# M304X.net
KiCad netlist of a schematic drawn in EAGLE
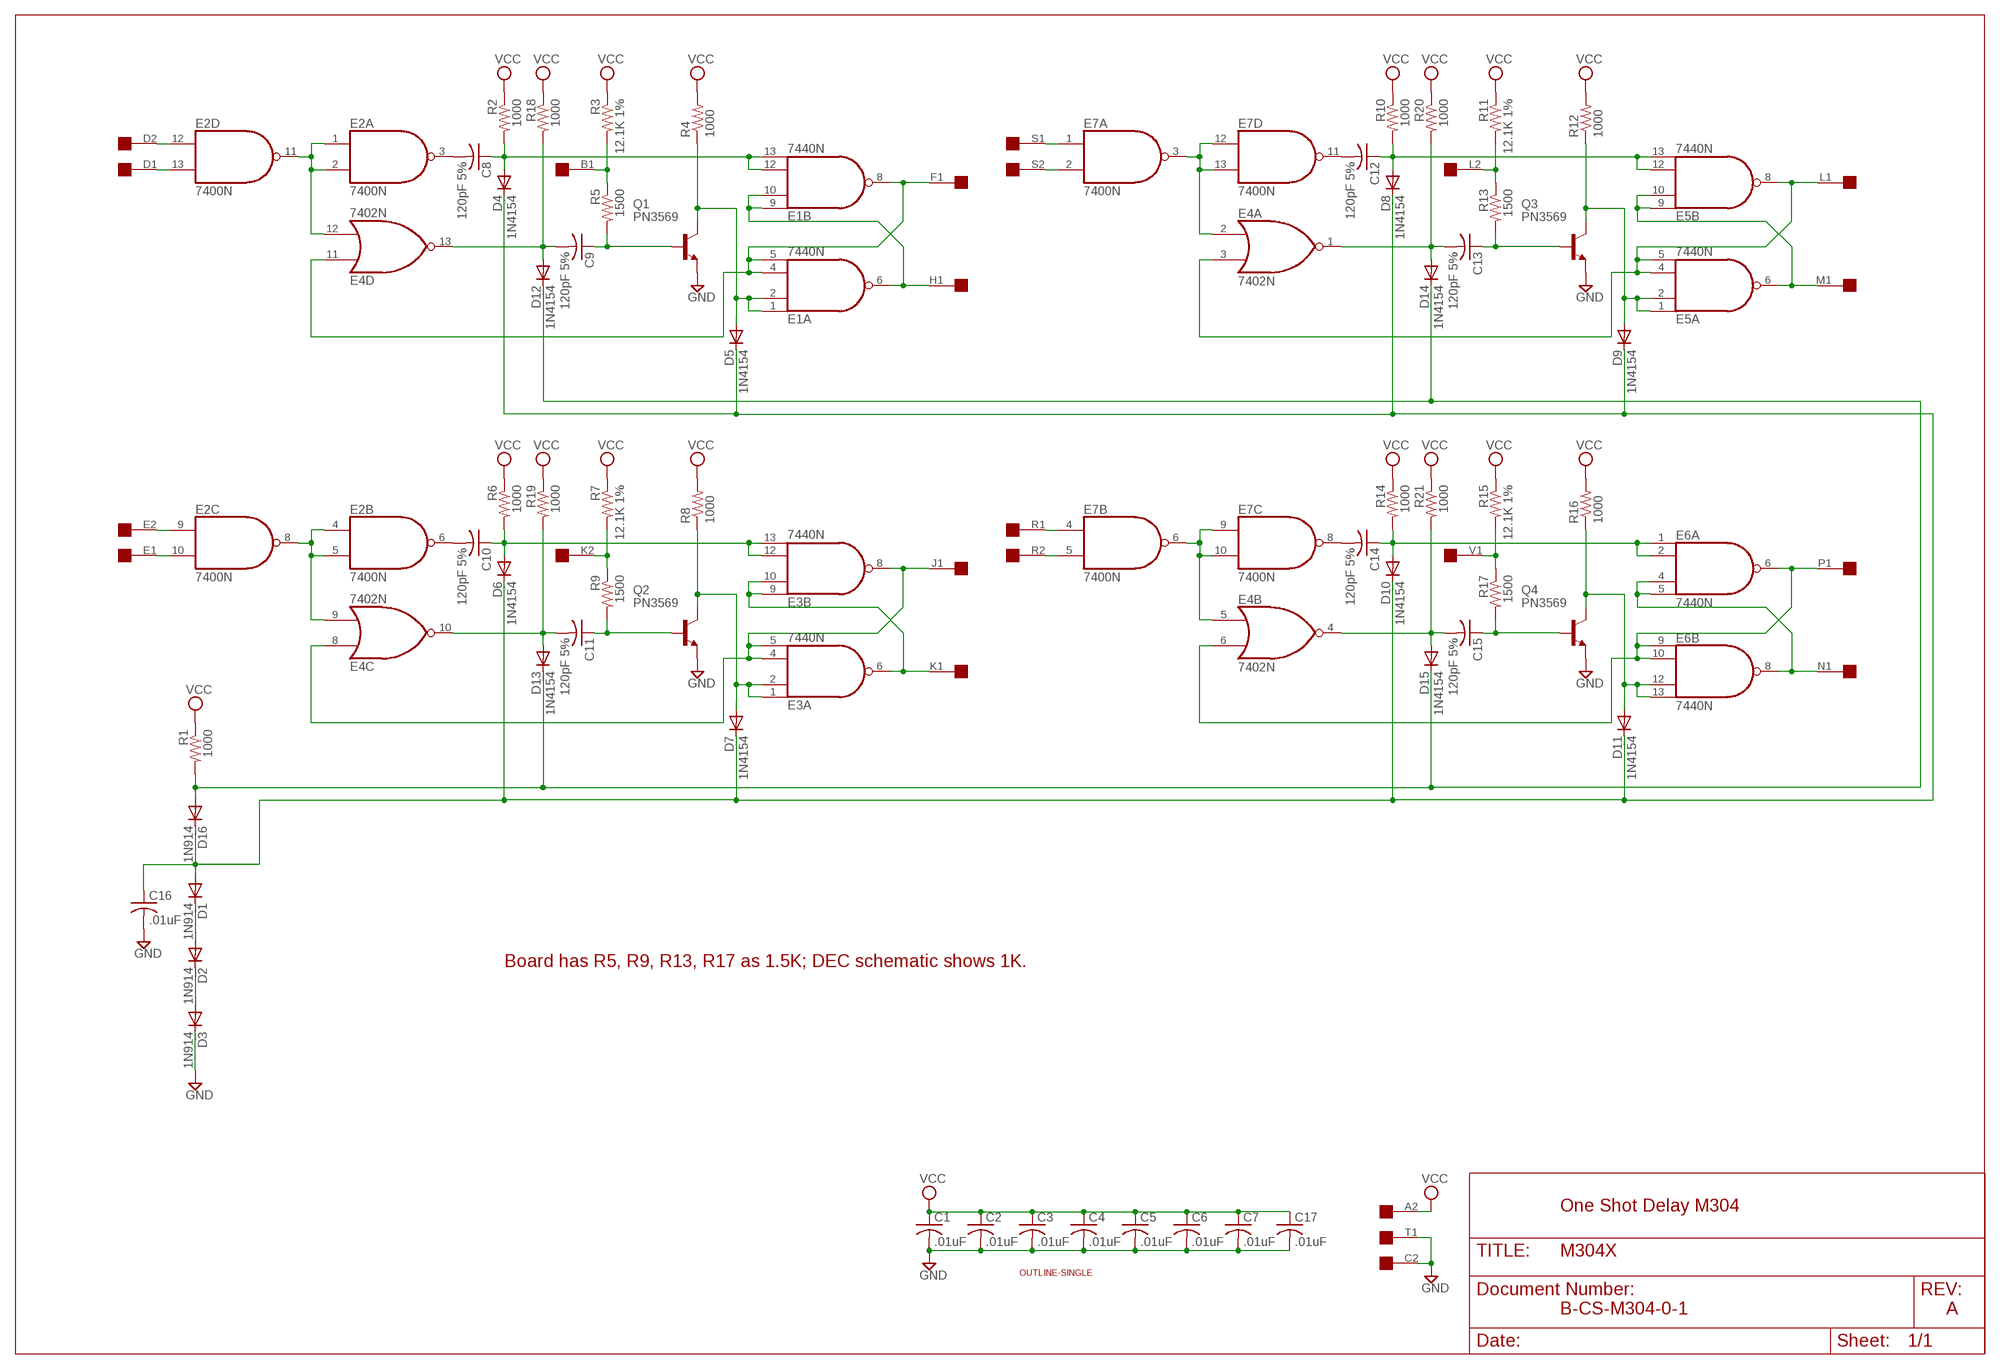
[diagram p0: schematic, sheet 1]

(export (version "E")
  (design (tool "Eeschema 10.0.6"))
  (components
    (comp (ref "C1")
      (value ".01uF")
      (footprint "eagle-import:C050-025X075")
      (libsource (lib "eagle-import") (part "C-US050-025X075"))
    )
    (comp (ref "C2")
      (value ".01uF")
      (footprint "eagle-import:C050-025X075")
      (libsource (lib "eagle-import") (part "C-US050-025X075"))
    )
    (comp (ref "C3")
      (value ".01uF")
      (footprint "eagle-import:C050-025X075")
      (libsource (lib "eagle-import") (part "C-US050-025X075"))
    )
    (comp (ref "C4")
      (value ".01uF")
      (footprint "eagle-import:C050-025X075")
      (libsource (lib "eagle-import") (part "C-US050-025X075"))
    )
    (comp (ref "C5")
      (value ".01uF")
      (footprint "eagle-import:C050-025X075")
      (libsource (lib "eagle-import") (part "C-US050-025X075"))
    )
    (comp (ref "C6")
      (value ".01uF")
      (footprint "eagle-import:C050-025X075")
      (libsource (lib "eagle-import") (part "C-US050-025X075"))
    )
    (comp (ref "C7")
      (value ".01uF")
      (footprint "eagle-import:C050-025X075")
      (libsource (lib "eagle-import") (part "C-US050-025X075"))
    )
    (comp (ref "C8")
      (value "120pF 5%")
      (footprint "eagle-import:C050-025X075")
      (libsource (lib "eagle-import") (part "C-US050-025X075"))
    )
    (comp (ref "C9")
      (value "120pF 5%")
      (footprint "eagle-import:C050-025X075")
      (libsource (lib "eagle-import") (part "C-US050-025X075"))
    )
    (comp (ref "C10")
      (value "120pF 5%")
      (footprint "eagle-import:C050-025X075")
      (libsource (lib "eagle-import") (part "C-US050-025X075"))
    )
    (comp (ref "C11")
      (value "120pF 5%")
      (footprint "eagle-import:C050-025X075")
      (libsource (lib "eagle-import") (part "C-US050-025X075"))
    )
    (comp (ref "C12")
      (value "120pF 5%")
      (footprint "eagle-import:C050-025X075")
      (libsource (lib "eagle-import") (part "C-US050-025X075"))
    )
    (comp (ref "C13")
      (value "120pF 5%")
      (footprint "eagle-import:C050-025X075")
      (libsource (lib "eagle-import") (part "C-US050-025X075"))
    )
    (comp (ref "C14")
      (value "120pF 5%")
      (footprint "eagle-import:C050-025X075")
      (libsource (lib "eagle-import") (part "C-US050-025X075"))
    )
    (comp (ref "C15")
      (value "120pF 5%")
      (footprint "eagle-import:C050-025X075")
      (libsource (lib "eagle-import") (part "C-US050-025X075"))
    )
    (comp (ref "C16")
      (value ".01uF")
      (footprint "eagle-import:C050-025X075")
      (libsource (lib "eagle-import") (part "C-US050-025X075"))
    )
    (comp (ref "C17")
      (value ".01uF")
      (footprint "eagle-import:C050-025X075")
      (libsource (lib "eagle-import") (part "C-US050-025X075"))
    )
    (comp (ref "D1")
      (value "1N914")
      (footprint "eagle-import:DO35-10")
      (libsource (lib "eagle-import") (part "1N4148DO35-10"))
    )
    (comp (ref "D2")
      (value "1N914")
      (footprint "eagle-import:DO35-10")
      (libsource (lib "eagle-import") (part "1N4148DO35-10"))
    )
    (comp (ref "D3")
      (value "1N914")
      (footprint "eagle-import:DO35-10")
      (libsource (lib "eagle-import") (part "1N4148DO35-10"))
    )
    (comp (ref "D4")
      (value "1N4154")
      (footprint "eagle-import:DO35-10")
      (libsource (lib "eagle-import") (part "1N4148DO35-10"))
    )
    (comp (ref "D5")
      (value "1N4154")
      (footprint "eagle-import:DO35-10")
      (libsource (lib "eagle-import") (part "1N4148DO35-10"))
    )
    (comp (ref "D6")
      (value "1N4154")
      (footprint "eagle-import:DO35-10")
      (libsource (lib "eagle-import") (part "1N4148DO35-10"))
    )
    (comp (ref "D7")
      (value "1N4154")
      (footprint "eagle-import:DO35-10")
      (libsource (lib "eagle-import") (part "1N4148DO35-10"))
    )
    (comp (ref "D8")
      (value "1N4154")
      (footprint "eagle-import:DO35-10")
      (libsource (lib "eagle-import") (part "1N4148DO35-10"))
    )
    (comp (ref "D9")
      (value "1N4154")
      (footprint "eagle-import:DO35-10")
      (libsource (lib "eagle-import") (part "1N4148DO35-10"))
    )
    (comp (ref "D10")
      (value "1N4154")
      (footprint "eagle-import:DO35-10")
      (libsource (lib "eagle-import") (part "1N4148DO35-10"))
    )
    (comp (ref "D11")
      (value "1N4154")
      (footprint "eagle-import:DO35-10")
      (libsource (lib "eagle-import") (part "1N4148DO35-10"))
    )
    (comp (ref "D12")
      (value "1N4154")
      (footprint "eagle-import:DO35-10")
      (libsource (lib "eagle-import") (part "1N4148DO35-10"))
    )
    (comp (ref "D13")
      (value "1N4154")
      (footprint "eagle-import:DO35-10")
      (libsource (lib "eagle-import") (part "1N4148DO35-10"))
    )
    (comp (ref "D14")
      (value "1N4154")
      (footprint "eagle-import:DO35-10")
      (libsource (lib "eagle-import") (part "1N4148DO35-10"))
    )
    (comp (ref "D15")
      (value "1N4154")
      (footprint "eagle-import:DO35-10")
      (libsource (lib "eagle-import") (part "1N4148DO35-10"))
    )
    (comp (ref "D16")
      (value "1N914")
      (footprint "eagle-import:DO35-10")
      (libsource (lib "eagle-import") (part "1N4148DO35-10"))
    )
    (comp (ref "E1")
      (value "7440N")
      (footprint "eagle-import:DIL14")
      (libsource (lib "eagle-import") (part "7420NS"))
    )
    (comp (ref "E2")
      (value "7400N")
      (footprint "eagle-import:DIL14")
      (libsource (lib "eagle-import") (part "7400N"))
    )
    (comp (ref "E3")
      (value "7440N")
      (footprint "eagle-import:DIL14")
      (libsource (lib "eagle-import") (part "7420NS"))
    )
    (comp (ref "E4")
      (value "7402N")
      (footprint "eagle-import:DIL14")
      (libsource (lib "eagle-import") (part "7402N"))
    )
    (comp (ref "E5")
      (value "7440N")
      (footprint "eagle-import:DIL14")
      (libsource (lib "eagle-import") (part "7420NS"))
    )
    (comp (ref "E6")
      (value "7440N")
      (footprint "eagle-import:DIL14")
      (libsource (lib "eagle-import") (part "7420NS"))
    )
    (comp (ref "E7")
      (value "7400N")
      (footprint "eagle-import:DIL14")
      (libsource (lib "eagle-import") (part "7400N"))
    )
    (comp (ref "Q1")
      (value "PN3569")
      (footprint "eagle-import:TO39")
      (libsource (lib "eagle-import") (part "-NPN-TO39-EBC2N3019"))
    )
    (comp (ref "Q2")
      (value "PN3569")
      (footprint "eagle-import:TO39")
      (libsource (lib "eagle-import") (part "-NPN-TO39-EBC2N3019"))
    )
    (comp (ref "Q3")
      (value "PN3569")
      (footprint "eagle-import:TO39")
      (libsource (lib "eagle-import") (part "-NPN-TO39-EBC2N3019"))
    )
    (comp (ref "Q4")
      (value "PN3569")
      (footprint "eagle-import:TO39")
      (libsource (lib "eagle-import") (part "-NPN-TO39-EBC2N3019"))
    )
    (comp (ref "R1")
      (value "1000")
      (footprint "eagle-import:0207_10")
      (libsource (lib "eagle-import") (part "R-US_0207/10"))
    )
    (comp (ref "R2")
      (value "1000")
      (footprint "eagle-import:0207_10")
      (libsource (lib "eagle-import") (part "R-US_0207/10"))
    )
    (comp (ref "R3")
      (value "12.1K 1%")
      (footprint "eagle-import:0207_15")
      (libsource (lib "eagle-import") (part "R-US_0207/15"))
    )
    (comp (ref "R4")
      (value "1000")
      (footprint "eagle-import:0207_10")
      (libsource (lib "eagle-import") (part "R-US_0207/10"))
    )
    (comp (ref "R5")
      (value "1500")
      (footprint "eagle-import:0207_10")
      (libsource (lib "eagle-import") (part "R-US_0207/10"))
    )
    (comp (ref "R6")
      (value "1000")
      (footprint "eagle-import:0207_10")
      (libsource (lib "eagle-import") (part "R-US_0207/10"))
    )
    (comp (ref "R7")
      (value "12.1K 1%")
      (footprint "eagle-import:0207_15")
      (libsource (lib "eagle-import") (part "R-US_0207/15"))
    )
    (comp (ref "R8")
      (value "1000")
      (footprint "eagle-import:0207_10")
      (libsource (lib "eagle-import") (part "R-US_0207/10"))
    )
    (comp (ref "R9")
      (value "1500")
      (footprint "eagle-import:0207_10")
      (libsource (lib "eagle-import") (part "R-US_0207/10"))
    )
    (comp (ref "R10")
      (value "1000")
      (footprint "eagle-import:0207_10")
      (libsource (lib "eagle-import") (part "R-US_0207/10"))
    )
    (comp (ref "R11")
      (value "12.1K 1%")
      (footprint "eagle-import:0207_15")
      (libsource (lib "eagle-import") (part "R-US_0207/15"))
    )
    (comp (ref "R12")
      (value "1000")
      (footprint "eagle-import:0207_10")
      (libsource (lib "eagle-import") (part "R-US_0207/10"))
    )
    (comp (ref "R13")
      (value "1500")
      (footprint "eagle-import:0207_10")
      (libsource (lib "eagle-import") (part "R-US_0207/10"))
    )
    (comp (ref "R14")
      (value "1000")
      (footprint "eagle-import:0207_10")
      (libsource (lib "eagle-import") (part "R-US_0207/10"))
    )
    (comp (ref "R15")
      (value "12.1K 1%")
      (footprint "eagle-import:0207_15")
      (libsource (lib "eagle-import") (part "R-US_0207/15"))
    )
    (comp (ref "R16")
      (value "1000")
      (footprint "eagle-import:0207_10")
      (libsource (lib "eagle-import") (part "R-US_0207/10"))
    )
    (comp (ref "R17")
      (value "1500")
      (footprint "eagle-import:0207_10")
      (libsource (lib "eagle-import") (part "R-US_0207/10"))
    )
    (comp (ref "R18")
      (value "1000")
      (footprint "eagle-import:0207_10")
      (libsource (lib "eagle-import") (part "R-US_0207/10"))
    )
    (comp (ref "R19")
      (value "1000")
      (footprint "eagle-import:0207_10")
      (libsource (lib "eagle-import") (part "R-US_0207/10"))
    )
    (comp (ref "R20")
      (value "1000")
      (footprint "eagle-import:0207_10")
      (libsource (lib "eagle-import") (part "R-US_0207/10"))
    )
    (comp (ref "R21")
      (value "1000")
      (footprint "eagle-import:0207_10")
      (libsource (lib "eagle-import") (part "R-US_0207/10"))
    )
    (comp (ref "U$1")
      (value "SINGLE")
      (footprint "eagle-import:EDGE-CON2")
      (libsource (lib "eagle-import") (part "SINGLE"))
    )
    (comp (ref "U$2")
      (value "OUTLINE-SINGLE")
      (footprint "eagle-import:SINGLE")
      (libsource (lib "eagle-import") (part "OUTLINE-SINGLE"))
    )
  )
  (nets
    (net (code "1") (name "GND") (class "Default")
      (node (ref "C1") (pin "2") (pinfunction "2_2") (pintype "passive"))
      (node (ref "C16") (pin "2") (pinfunction "2_2") (pintype "passive"))
      (node (ref "C17") (pin "2") (pinfunction "2_2") (pintype "passive"))
      (node (ref "C2") (pin "2") (pinfunction "2_2") (pintype "passive"))
      (node (ref "C3") (pin "2") (pinfunction "2_2") (pintype "passive"))
      (node (ref "C4") (pin "2") (pinfunction "2_2") (pintype "passive"))
      (node (ref "C5") (pin "2") (pinfunction "2_2") (pintype "passive"))
      (node (ref "C6") (pin "2") (pinfunction "2_2") (pintype "passive"))
      (node (ref "C7") (pin "2") (pinfunction "2_2") (pintype "passive"))
      (node (ref "D3") (pin "C") (pinfunction "C_C") (pintype "passive"))
      (node (ref "Q1") (pin "1") (pinfunction "E_1") (pintype "passive"))
      (node (ref "Q2") (pin "1") (pinfunction "E_1") (pintype "passive"))
      (node (ref "Q3") (pin "1") (pinfunction "E_1") (pintype "passive"))
      (node (ref "Q4") (pin "1") (pinfunction "E_1") (pintype "passive"))
      (node (ref "U$1") (pin "C2") (pinfunction "1_C2") (pintype "bidirectional"))
      (node (ref "U$1") (pin "T1") (pinfunction "1_T1") (pintype "bidirectional"))
    )
    (net (code "2") (name "Net-(C16-Pad1)") (class "Default")
      (node (ref "C16") (pin "1") (pinfunction "1_1") (pintype "passive"))
      (node (ref "D1") (pin "A") (pinfunction "A_A") (pintype "passive"))
      (node (ref "D10") (pin "C") (pinfunction "C_C") (pintype "passive"))
      (node (ref "D11") (pin "C") (pinfunction "C_C") (pintype "passive"))
      (node (ref "D16") (pin "C") (pinfunction "C_C") (pintype "passive"))
      (node (ref "D4") (pin "C") (pinfunction "C_C") (pintype "passive"))
      (node (ref "D5") (pin "C") (pinfunction "C_C") (pintype "passive"))
      (node (ref "D6") (pin "C") (pinfunction "C_C") (pintype "passive"))
      (node (ref "D7") (pin "C") (pinfunction "C_C") (pintype "passive"))
      (node (ref "D8") (pin "C") (pinfunction "C_C") (pintype "passive"))
      (node (ref "D9") (pin "C") (pinfunction "C_C") (pintype "passive"))
    )
    (net (code "3") (name "Net-(D1-PadC)") (class "Default")
      (node (ref "D1") (pin "C") (pinfunction "C_C") (pintype "passive"))
      (node (ref "D2") (pin "A") (pinfunction "A_A") (pintype "passive"))
    )
    (net (code "4") (name "Net-(D2-PadC)") (class "Default")
      (node (ref "D2") (pin "C") (pinfunction "C_C") (pintype "passive"))
      (node (ref "D3") (pin "A") (pinfunction "A_A") (pintype "passive"))
    )
    (net (code "5") (name "Net-(D12-PadC)") (class "Default")
      (node (ref "D12") (pin "C") (pinfunction "C_C") (pintype "passive"))
      (node (ref "D13") (pin "C") (pinfunction "C_C") (pintype "passive"))
      (node (ref "D14") (pin "C") (pinfunction "C_C") (pintype "passive"))
      (node (ref "D15") (pin "C") (pinfunction "C_C") (pintype "passive"))
      (node (ref "D16") (pin "A") (pinfunction "A_A") (pintype "passive"))
      (node (ref "R1") (pin "2") (pinfunction "2_2") (pintype "passive"))
    )
    (net (code "6") (name "Net-(E1A-I0)") (class "Default")
      (node (ref "D5") (pin "A") (pinfunction "A_A") (pintype "passive"))
      (node (ref "E1") (pin "1") (pinfunction "I0_1") (pintype "input"))
      (node (ref "E1") (pin "2") (pinfunction "I1_2") (pintype "input"))
      (node (ref "Q1") (pin "3") (pinfunction "C_3") (pintype "passive"))
      (node (ref "R4") (pin "1") (pinfunction "1_1") (pintype "passive"))
    )
    (net (code "7") (name "Net-(E1A-I2)") (class "Default")
      (node (ref "E1") (pin "4") (pinfunction "I2_4") (pintype "input"))
      (node (ref "E1") (pin "5") (pinfunction "I3_5") (pintype "input"))
      (node (ref "E1") (pin "8") (pinfunction "O_8") (pintype "output"))
      (node (ref "E4") (pin "11") (pinfunction "I0_11") (pintype "input"))
      (node (ref "U$1") (pin "F1") (pinfunction "1_F1") (pintype "bidirectional"))
    )
    (net (code "8") (name "Net-(E1A-O)") (class "Default")
      (node (ref "E1") (pin "10") (pinfunction "I1_10") (pintype "input"))
      (node (ref "E1") (pin "6") (pinfunction "O_6") (pintype "output"))
      (node (ref "E1") (pin "9") (pinfunction "I0_9") (pintype "input"))
      (node (ref "U$1") (pin "H1") (pinfunction "1_H1") (pintype "bidirectional"))
    )
    (net (code "9") (name "Net-(E1B-I2)") (class "Default")
      (node (ref "C8") (pin "1") (pinfunction "1_1") (pintype "passive"))
      (node (ref "D4") (pin "A") (pinfunction "A_A") (pintype "passive"))
      (node (ref "E1") (pin "12") (pinfunction "I2_12") (pintype "input"))
      (node (ref "E1") (pin "13") (pinfunction "I3_13") (pintype "input"))
      (node (ref "R2") (pin "2") (pinfunction "2_2") (pintype "passive"))
    )
    (net (code "10") (name "Net-(E2A-I0)") (class "Default")
      (node (ref "E2") (pin "1") (pinfunction "I0_1") (pintype "input"))
      (node (ref "E2") (pin "11") (pinfunction "O_11") (pintype "output"))
      (node (ref "E2") (pin "2") (pinfunction "I1_2") (pintype "input"))
      (node (ref "E4") (pin "12") (pinfunction "I1_12") (pintype "input"))
    )
    (net (code "11") (name "Net-(E2A-O)") (class "Default")
      (node (ref "C8") (pin "2") (pinfunction "2_2") (pintype "passive"))
      (node (ref "E2") (pin "3") (pinfunction "O_3") (pintype "output"))
    )
    (net (code "12") (name "Net-(E2B-I0)") (class "Default")
      (node (ref "E2") (pin "4") (pinfunction "I0_4") (pintype "input"))
      (node (ref "E2") (pin "5") (pinfunction "I1_5") (pintype "input"))
      (node (ref "E2") (pin "8") (pinfunction "O_8") (pintype "output"))
      (node (ref "E4") (pin "9") (pinfunction "I1_9") (pintype "input"))
    )
    (net (code "13") (name "Net-(E2B-O)") (class "Default")
      (node (ref "C10") (pin "2") (pinfunction "2_2") (pintype "passive"))
      (node (ref "E2") (pin "6") (pinfunction "O_6") (pintype "output"))
    )
    (net (code "14") (name "Net-(E2C-I0)") (class "Default")
      (node (ref "E2") (pin "9") (pinfunction "I0_9") (pintype "input"))
      (node (ref "U$1") (pin "E2") (pinfunction "1_E2") (pintype "bidirectional"))
    )
    (net (code "15") (name "Net-(E2C-I1)") (class "Default")
      (node (ref "E2") (pin "10") (pinfunction "I1_10") (pintype "input"))
      (node (ref "U$1") (pin "E1") (pinfunction "1_E1") (pintype "bidirectional"))
    )
    (net (code "16") (name "Net-(E2D-I0)") (class "Default")
      (node (ref "E2") (pin "12") (pinfunction "I0_12") (pintype "input"))
      (node (ref "U$1") (pin "D2") (pinfunction "1_D2") (pintype "bidirectional"))
    )
    (net (code "17") (name "Net-(E2D-I1)") (class "Default")
      (node (ref "E2") (pin "13") (pinfunction "I1_13") (pintype "input"))
      (node (ref "U$1") (pin "D1") (pinfunction "1_D1") (pintype "bidirectional"))
    )
    (net (code "18") (name "Net-(E3A-I0)") (class "Default")
      (node (ref "D7") (pin "A") (pinfunction "A_A") (pintype "passive"))
      (node (ref "E3") (pin "1") (pinfunction "I0_1") (pintype "input"))
      (node (ref "E3") (pin "2") (pinfunction "I1_2") (pintype "input"))
      (node (ref "Q2") (pin "3") (pinfunction "C_3") (pintype "passive"))
      (node (ref "R8") (pin "1") (pinfunction "1_1") (pintype "passive"))
    )
    (net (code "19") (name "Net-(E3A-I2)") (class "Default")
      (node (ref "E3") (pin "4") (pinfunction "I2_4") (pintype "input"))
      (node (ref "E3") (pin "5") (pinfunction "I3_5") (pintype "input"))
      (node (ref "E3") (pin "8") (pinfunction "O_8") (pintype "output"))
      (node (ref "E4") (pin "8") (pinfunction "I0_8") (pintype "input"))
      (node (ref "U$1") (pin "J1") (pinfunction "1_J1") (pintype "bidirectional"))
    )
    (net (code "20") (name "Net-(E3A-O)") (class "Default")
      (node (ref "E3") (pin "10") (pinfunction "I1_10") (pintype "input"))
      (node (ref "E3") (pin "6") (pinfunction "O_6") (pintype "output"))
      (node (ref "E3") (pin "9") (pinfunction "I0_9") (pintype "input"))
      (node (ref "U$1") (pin "K1") (pinfunction "1_K1") (pintype "bidirectional"))
    )
    (net (code "21") (name "Net-(E3B-I2)") (class "Default")
      (node (ref "C10") (pin "1") (pinfunction "1_1") (pintype "passive"))
      (node (ref "D6") (pin "A") (pinfunction "A_A") (pintype "passive"))
      (node (ref "E3") (pin "12") (pinfunction "I2_12") (pintype "input"))
      (node (ref "E3") (pin "13") (pinfunction "I3_13") (pintype "input"))
      (node (ref "R6") (pin "2") (pinfunction "2_2") (pintype "passive"))
    )
    (net (code "22") (name "Net-(E4A-I0)") (class "Default")
      (node (ref "E4") (pin "2") (pinfunction "I0_2") (pintype "input"))
      (node (ref "E7") (pin "12") (pinfunction "I0_12") (pintype "input"))
      (node (ref "E7") (pin "13") (pinfunction "I1_13") (pintype "input"))
      (node (ref "E7") (pin "3") (pinfunction "O_3") (pintype "output"))
    )
    (net (code "23") (name "Net-(E4A-I1)") (class "Default")
      (node (ref "E4") (pin "3") (pinfunction "I1_3") (pintype "input"))
      (node (ref "E5") (pin "4") (pinfunction "I2_4") (pintype "input"))
      (node (ref "E5") (pin "5") (pinfunction "I3_5") (pintype "input"))
      (node (ref "E5") (pin "8") (pinfunction "O_8") (pintype "output"))
      (node (ref "U$1") (pin "L1") (pinfunction "1_L1") (pintype "bidirectional"))
    )
    (net (code "24") (name "Net-(E4A-O)") (class "Default")
      (node (ref "C13") (pin "2") (pinfunction "2_2") (pintype "passive"))
      (node (ref "D14") (pin "A") (pinfunction "A_A") (pintype "passive"))
      (node (ref "E4") (pin "1") (pinfunction "O_1") (pintype "output"))
      (node (ref "R20") (pin "2") (pinfunction "2_2") (pintype "passive"))
    )
    (net (code "25") (name "Net-(E4B-I0)") (class "Default")
      (node (ref "E4") (pin "5") (pinfunction "I0_5") (pintype "input"))
      (node (ref "E7") (pin "10") (pinfunction "I1_10") (pintype "input"))
      (node (ref "E7") (pin "6") (pinfunction "O_6") (pintype "output"))
      (node (ref "E7") (pin "9") (pinfunction "I0_9") (pintype "input"))
    )
    (net (code "26") (name "Net-(E4B-I1)") (class "Default")
      (node (ref "E4") (pin "6") (pinfunction "I1_6") (pintype "input"))
      (node (ref "E6") (pin "10") (pinfunction "I1_10") (pintype "input"))
      (node (ref "E6") (pin "6") (pinfunction "O_6") (pintype "output"))
      (node (ref "E6") (pin "9") (pinfunction "I0_9") (pintype "input"))
      (node (ref "U$1") (pin "P1") (pinfunction "1_P1") (pintype "bidirectional"))
    )
    (net (code "27") (name "Net-(E4B-O)") (class "Default")
      (node (ref "C15") (pin "2") (pinfunction "2_2") (pintype "passive"))
      (node (ref "D15") (pin "A") (pinfunction "A_A") (pintype "passive"))
      (node (ref "E4") (pin "4") (pinfunction "O_4") (pintype "output"))
      (node (ref "R21") (pin "2") (pinfunction "2_2") (pintype "passive"))
    )
    (net (code "28") (name "Net-(E4C-O)") (class "Default")
      (node (ref "C11") (pin "2") (pinfunction "2_2") (pintype "passive"))
      (node (ref "D13") (pin "A") (pinfunction "A_A") (pintype "passive"))
      (node (ref "E4") (pin "10") (pinfunction "O_10") (pintype "output"))
      (node (ref "R19") (pin "2") (pinfunction "2_2") (pintype "passive"))
    )
    (net (code "29") (name "Net-(E4D-O)") (class "Default")
      (node (ref "C9") (pin "2") (pinfunction "2_2") (pintype "passive"))
      (node (ref "D12") (pin "A") (pinfunction "A_A") (pintype "passive"))
      (node (ref "E4") (pin "13") (pinfunction "O_13") (pintype "output"))
      (node (ref "R18") (pin "2") (pinfunction "2_2") (pintype "passive"))
    )
    (net (code "30") (name "Net-(E5A-I0)") (class "Default")
      (node (ref "D9") (pin "A") (pinfunction "A_A") (pintype "passive"))
      (node (ref "E5") (pin "1") (pinfunction "I0_1") (pintype "input"))
      (node (ref "E5") (pin "2") (pinfunction "I1_2") (pintype "input"))
      (node (ref "Q3") (pin "3") (pinfunction "C_3") (pintype "passive"))
      (node (ref "R12") (pin "1") (pinfunction "1_1") (pintype "passive"))
    )
    (net (code "31") (name "Net-(E5A-O)") (class "Default")
      (node (ref "E5") (pin "10") (pinfunction "I1_10") (pintype "input"))
      (node (ref "E5") (pin "6") (pinfunction "O_6") (pintype "output"))
      (node (ref "E5") (pin "9") (pinfunction "I0_9") (pintype "input"))
      (node (ref "U$1") (pin "M1") (pinfunction "1_M1") (pintype "bidirectional"))
    )
    (net (code "32") (name "Net-(E5B-I2)") (class "Default")
      (node (ref "C12") (pin "1") (pinfunction "1_1") (pintype "passive"))
      (node (ref "D8") (pin "A") (pinfunction "A_A") (pintype "passive"))
      (node (ref "E5") (pin "12") (pinfunction "I2_12") (pintype "input"))
      (node (ref "E5") (pin "13") (pinfunction "I3_13") (pintype "input"))
      (node (ref "R10") (pin "2") (pinfunction "2_2") (pintype "passive"))
    )
    (net (code "33") (name "Net-(E6A-I0)") (class "Default")
      (node (ref "C14") (pin "1") (pinfunction "1_1") (pintype "passive"))
      (node (ref "D10") (pin "A") (pinfunction "A_A") (pintype "passive"))
      (node (ref "E6") (pin "1") (pinfunction "I0_1") (pintype "input"))
      (node (ref "E6") (pin "2") (pinfunction "I1_2") (pintype "input"))
      (node (ref "R14") (pin "2") (pinfunction "2_2") (pintype "passive"))
    )
    (net (code "34") (name "Net-(E6A-I2)") (class "Default")
      (node (ref "E6") (pin "4") (pinfunction "I2_4") (pintype "input"))
      (node (ref "E6") (pin "5") (pinfunction "I3_5") (pintype "input"))
      (node (ref "E6") (pin "8") (pinfunction "O_8") (pintype "output"))
      (node (ref "U$1") (pin "N1") (pinfunction "1_N1") (pintype "bidirectional"))
    )
    (net (code "35") (name "Net-(E6B-I2)") (class "Default")
      (node (ref "D11") (pin "A") (pinfunction "A_A") (pintype "passive"))
      (node (ref "E6") (pin "12") (pinfunction "I2_12") (pintype "input"))
      (node (ref "E6") (pin "13") (pinfunction "I3_13") (pintype "input"))
      (node (ref "Q4") (pin "3") (pinfunction "C_3") (pintype "passive"))
      (node (ref "R16") (pin "1") (pinfunction "1_1") (pintype "passive"))
    )
    (net (code "36") (name "Net-(E7A-I0)") (class "Default")
      (node (ref "E7") (pin "1") (pinfunction "I0_1") (pintype "input"))
      (node (ref "U$1") (pin "S1") (pinfunction "1_S1") (pintype "bidirectional"))
    )
    (net (code "37") (name "Net-(E7A-I1)") (class "Default")
      (node (ref "E7") (pin "2") (pinfunction "I1_2") (pintype "input"))
      (node (ref "U$1") (pin "S2") (pinfunction "1_S2") (pintype "bidirectional"))
    )
    (net (code "38") (name "Net-(E7B-I0)") (class "Default")
      (node (ref "E7") (pin "4") (pinfunction "I0_4") (pintype "input"))
      (node (ref "U$1") (pin "R1") (pinfunction "1_R1") (pintype "bidirectional"))
    )
    (net (code "39") (name "Net-(E7B-I1)") (class "Default")
      (node (ref "E7") (pin "5") (pinfunction "I1_5") (pintype "input"))
      (node (ref "U$1") (pin "R2") (pinfunction "1_R2") (pintype "bidirectional"))
    )
    (net (code "40") (name "Net-(E7C-O)") (class "Default")
      (node (ref "C14") (pin "2") (pinfunction "2_2") (pintype "passive"))
      (node (ref "E7") (pin "8") (pinfunction "O_8") (pintype "output"))
    )
    (net (code "41") (name "Net-(E7D-O)") (class "Default")
      (node (ref "C12") (pin "2") (pinfunction "2_2") (pintype "passive"))
      (node (ref "E7") (pin "11") (pinfunction "O_11") (pintype "output"))
    )
    (net (code "42") (name "Net-(Q1-B)") (class "Default")
      (node (ref "C9") (pin "1") (pinfunction "1_1") (pintype "passive"))
      (node (ref "Q1") (pin "2") (pinfunction "B_2") (pintype "passive"))
      (node (ref "R5") (pin "2") (pinfunction "2_2") (pintype "passive"))
    )
    (net (code "43") (name "Net-(Q2-B)") (class "Default")
      (node (ref "C11") (pin "1") (pinfunction "1_1") (pintype "passive"))
      (node (ref "Q2") (pin "2") (pinfunction "B_2") (pintype "passive"))
      (node (ref "R9") (pin "2") (pinfunction "2_2") (pintype "passive"))
    )
    (net (code "44") (name "Net-(Q3-B)") (class "Default")
      (node (ref "C13") (pin "1") (pinfunction "1_1") (pintype "passive"))
      (node (ref "Q3") (pin "2") (pinfunction "B_2") (pintype "passive"))
      (node (ref "R13") (pin "2") (pinfunction "2_2") (pintype "passive"))
    )
    (net (code "45") (name "Net-(Q4-B)") (class "Default")
      (node (ref "C15") (pin "1") (pinfunction "1_1") (pintype "passive"))
      (node (ref "Q4") (pin "2") (pinfunction "B_2") (pintype "passive"))
      (node (ref "R17") (pin "2") (pinfunction "2_2") (pintype "passive"))
    )
    (net (code "46") (name "Net-(U$1AI-1)") (class "Default")
      (node (ref "R15") (pin "2") (pinfunction "2_2") (pintype "passive"))
      (node (ref "R17") (pin "1") (pinfunction "1_1") (pintype "passive"))
      (node (ref "U$1") (pin "V1") (pinfunction "1_V1") (pintype "bidirectional"))
    )
    (net (code "47") (name "Net-(U$1C-1)") (class "Default")
      (node (ref "R3") (pin "2") (pinfunction "2_2") (pintype "passive"))
      (node (ref "R5") (pin "1") (pinfunction "1_1") (pintype "passive"))
      (node (ref "U$1") (pin "B1") (pinfunction "1_B1") (pintype "bidirectional"))
    )
    (net (code "48") (name "Net-(U$1R-1)") (class "Default")
      (node (ref "R7") (pin "2") (pinfunction "2_2") (pintype "passive"))
      (node (ref "R9") (pin "1") (pinfunction "1_1") (pintype "passive"))
      (node (ref "U$1") (pin "K2") (pinfunction "1_K2") (pintype "bidirectional"))
    )
    (net (code "49") (name "Net-(U$1T-1)") (class "Default")
      (node (ref "R11") (pin "2") (pinfunction "2_2") (pintype "passive"))
      (node (ref "R13") (pin "1") (pinfunction "1_1") (pintype "passive"))
      (node (ref "U$1") (pin "L2") (pinfunction "1_L2") (pintype "bidirectional"))
    )
    (net (code "50") (name "VCC") (class "Default")
      (node (ref "C1") (pin "1") (pinfunction "1_1") (pintype "passive"))
      (node (ref "C17") (pin "1") (pinfunction "1_1") (pintype "passive"))
      (node (ref "C2") (pin "1") (pinfunction "1_1") (pintype "passive"))
      (node (ref "C3") (pin "1") (pinfunction "1_1") (pintype "passive"))
      (node (ref "C4") (pin "1") (pinfunction "1_1") (pintype "passive"))
      (node (ref "C5") (pin "1") (pinfunction "1_1") (pintype "passive"))
      (node (ref "C6") (pin "1") (pinfunction "1_1") (pintype "passive"))
      (node (ref "C7") (pin "1") (pinfunction "1_1") (pintype "passive"))
      (node (ref "R1") (pin "1") (pinfunction "1_1") (pintype "passive"))
      (node (ref "R10") (pin "1") (pinfunction "1_1") (pintype "passive"))
      (node (ref "R11") (pin "1") (pinfunction "1_1") (pintype "passive"))
      (node (ref "R12") (pin "2") (pinfunction "2_2") (pintype "passive"))
      (node (ref "R14") (pin "1") (pinfunction "1_1") (pintype "passive"))
      (node (ref "R15") (pin "1") (pinfunction "1_1") (pintype "passive"))
      (node (ref "R16") (pin "2") (pinfunction "2_2") (pintype "passive"))
      (node (ref "R18") (pin "1") (pinfunction "1_1") (pintype "passive"))
      (node (ref "R19") (pin "1") (pinfunction "1_1") (pintype "passive"))
      (node (ref "R2") (pin "1") (pinfunction "1_1") (pintype "passive"))
      (node (ref "R20") (pin "1") (pinfunction "1_1") (pintype "passive"))
      (node (ref "R21") (pin "1") (pinfunction "1_1") (pintype "passive"))
      (node (ref "R3") (pin "1") (pinfunction "1_1") (pintype "passive"))
      (node (ref "R4") (pin "2") (pinfunction "2_2") (pintype "passive"))
      (node (ref "R6") (pin "1") (pinfunction "1_1") (pintype "passive"))
      (node (ref "R7") (pin "1") (pinfunction "1_1") (pintype "passive"))
      (node (ref "R8") (pin "2") (pinfunction "2_2") (pintype "passive"))
      (node (ref "U$1") (pin "A2") (pinfunction "1_A2") (pintype "bidirectional"))
    )
  )
)
